# source_pcb.net
KiCad netlist of a schematic drawn in EasyEDA Pro
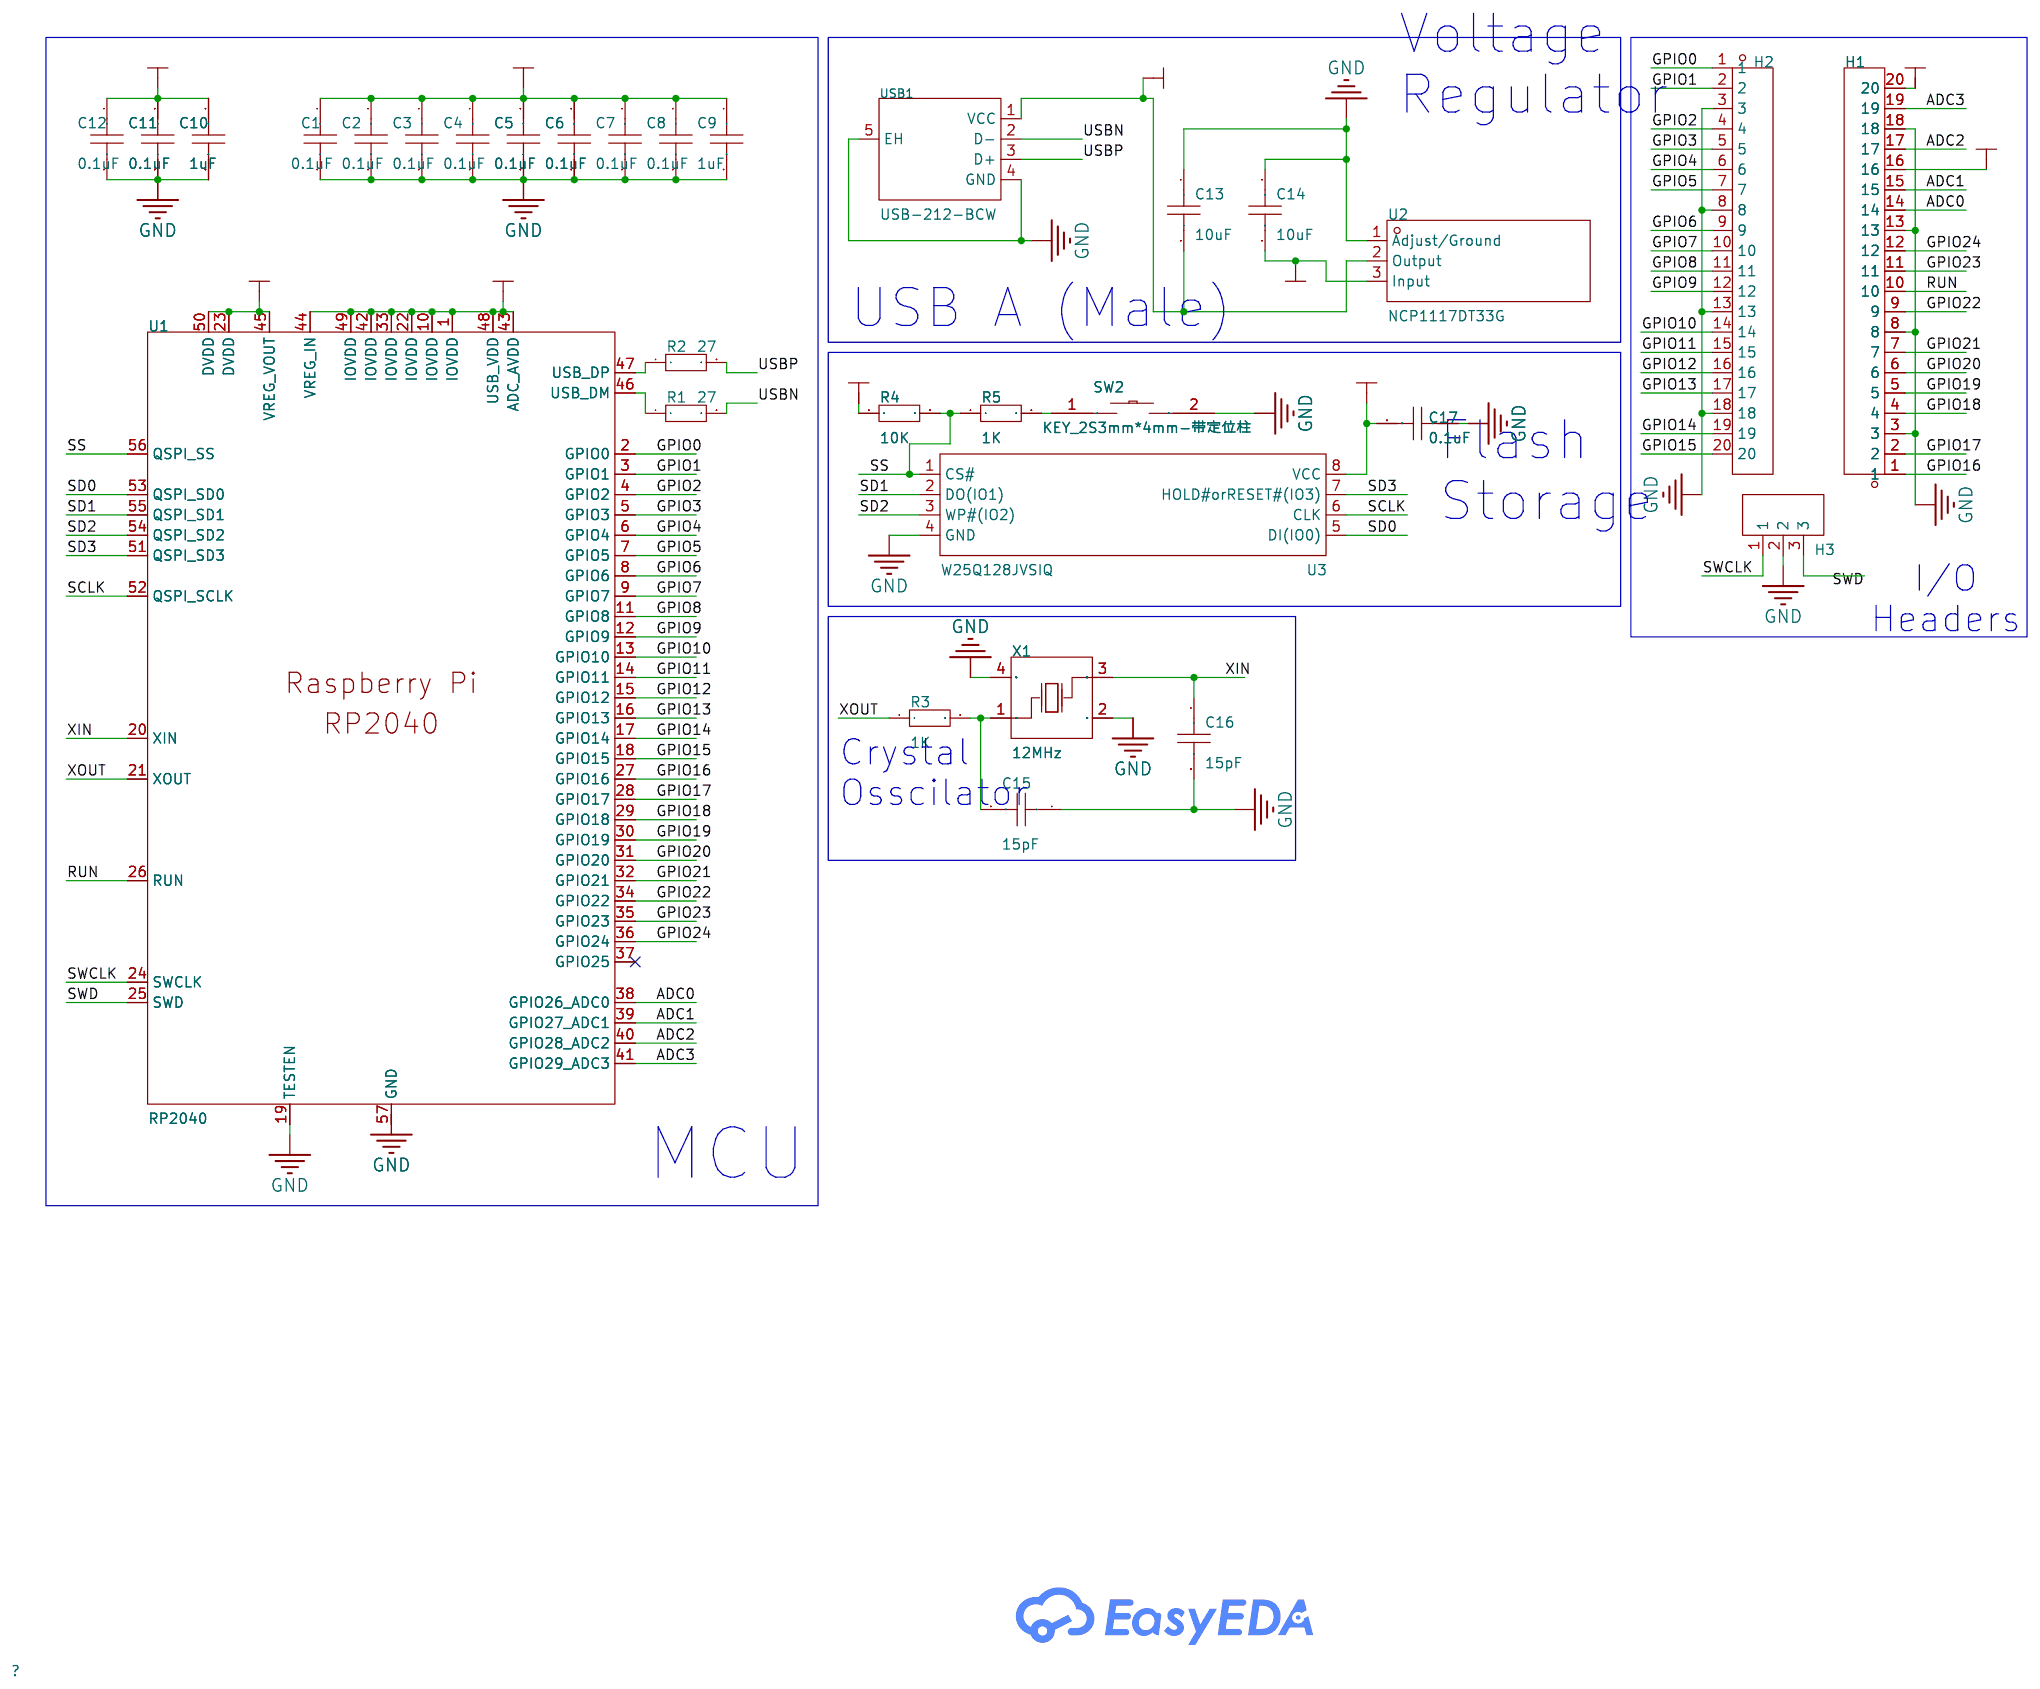
[diagram p0: schematic sheet]

(export (version "E")
  (design (tool "Eeschema 10.0.6"))
  (components
    (comp (ref "C1")
      (value "100nF")
      (footprint "easyedapro:C0603")
      (libsource (lib "easyedapro") (part "CAP"))
    )
    (comp (ref "C2")
      (value "100nF")
      (footprint "easyedapro:C0603")
      (libsource (lib "easyedapro") (part "CAP"))
    )
    (comp (ref "C3")
      (value "100nF")
      (footprint "easyedapro:C0603")
      (libsource (lib "easyedapro") (part "CAP"))
    )
    (comp (ref "C4")
      (value "100nF")
      (footprint "easyedapro:C0603")
      (libsource (lib "easyedapro") (part "CAP"))
    )
    (comp (ref "C5")
      (value "100nF")
      (footprint "easyedapro:C0603")
      (libsource (lib "easyedapro") (part "CAP"))
    )
    (comp (ref "C6")
      (value "100nF")
      (footprint "easyedapro:C0603")
      (libsource (lib "easyedapro") (part "CAP"))
    )
    (comp (ref "C7")
      (value "100nF")
      (footprint "easyedapro:C0603")
      (libsource (lib "easyedapro") (part "CAP"))
    )
    (comp (ref "C8")
      (value "100nF")
      (footprint "easyedapro:C0603")
      (libsource (lib "easyedapro") (part "CAP"))
    )
    (comp (ref "C9")
      (value "100nF")
      (footprint "easyedapro:C0603")
      (libsource (lib "easyedapro") (part "CAP"))
    )
    (comp (ref "C10")
      (value "100nF")
      (footprint "easyedapro:C0603")
      (libsource (lib "easyedapro") (part "CAP"))
    )
    (comp (ref "C11")
      (value "100nF")
      (footprint "easyedapro:C0603")
      (libsource (lib "easyedapro") (part "CAP"))
    )
    (comp (ref "C12")
      (value "100nF")
      (footprint "easyedapro:C0603")
      (libsource (lib "easyedapro") (part "CAP"))
    )
    (comp (ref "C13")
      (value "100nF")
      (footprint "easyedapro:C0603")
      (libsource (lib "easyedapro") (part "CAP"))
    )
    (comp (ref "C14")
      (value "100nF")
      (footprint "easyedapro:C0603")
      (libsource (lib "easyedapro") (part "CAP"))
    )
    (comp (ref "C15")
      (value "100nF")
      (footprint "easyedapro:C0603")
      (libsource (lib "easyedapro") (part "CAP"))
    )
    (comp (ref "C16")
      (value "100nF")
      (footprint "easyedapro:C0603")
      (libsource (lib "easyedapro") (part "CAP"))
    )
    (comp (ref "C17")
      (value "100nF")
      (footprint "easyedapro:C0603")
      (libsource (lib "easyedapro") (part "CAP"))
    )
    (comp (ref "H1")
      (value "~")
      (footprint "easyedapro:HDR-TH_20P-P2.54-V-M-1")
      (libsource (lib "easyedapro") (part "HDR_2.54-1x20P"))
    )
    (comp (ref "H2")
      (value "~")
      (footprint "easyedapro:HDR-TH_20P-P2.54-V-M-1")
      (libsource (lib "easyedapro") (part "HDR_2.54-1x20P"))
    )
    (comp (ref "H3")
      (value "~")
      (footprint "easyedapro:HDR-TH_3P-P2.54-V-M")
      (libsource (lib "easyedapro") (part "PZ254V-11-03P_C2937625"))
    )
    (comp (ref "R1") (value "10K") (footprint "easyedapro:R0603") (libsource (lib "easyedapro") (part "Res")))
    (comp (ref "R2") (value "10K") (footprint "easyedapro:R0603") (libsource (lib "easyedapro") (part "Res")))
    (comp (ref "R3") (value "10K") (footprint "easyedapro:R0603") (libsource (lib "easyedapro") (part "Res")))
    (comp (ref "R4") (value "10K") (footprint "easyedapro:R0603") (libsource (lib "easyedapro") (part "Res")))
    (comp (ref "R5") (value "10K") (footprint "easyedapro:R0603") (libsource (lib "easyedapro") (part "Res")))
    (comp (ref "SW2")
      (value "KEY_2S3mm*4mm-带定位柱")
      (footprint "easyedapro:KEY-SMD_L4.0-W3.7-LS4.8")
      (libsource (lib "easyedapro") (part "KEY_2S3MM*4MM-带定位柱"))
    )
    (comp (ref "U1")
      (value "RP2040")
      (footprint "easyedapro:QFN-56_L7.0-W7.0-P0.40-TL-EP4.0")
      (fields (field (name "Manufacturer") "Raspberry Pi(树莓派)"))
      (libsource (lib "easyedapro") (part "RP2040_C2961140"))
    )
    (comp (ref "U2")
      (value "NCP1117DT33G")
      (footprint "easyedapro:TO-252_L6.5-W6.1-P4.58-LS9.9-BR")
      (fields (field (name "Manufacturer") "onsemi(安森美)"))
      (libsource (lib "easyedapro") (part "NCP1117DT33G"))
    )
    (comp (ref "U3")
      (value "W25Q128JVSIQ")
      (footprint "easyedapro:SOIC-8_L5.3-W5.3-P1.27-LS8.0-BL")
      (fields (field (name "Manufacturer") "Winbond(华邦)"))
      (libsource (lib "easyedapro") (part "W25Q128JVSIQ"))
    )
    (comp (ref "USB1")
      (value "USB-212-BCW")
      (footprint "easyedapro:USB-A-SMD_USB-212-BCW")
      (fields (field (name "Manufacturer") "XUNPU(讯普)"))
      (libsource (lib "easyedapro") (part "USB-212-BCW"))
    )
    (comp (ref "X1")
      (value "12MHz")
      (footprint "easyedapro:CRYSTAL-SMD_4P-L3.2-W2.5-BL")
      (fields (field (name "Manufacturer Part") "X322512MSB4SI") (field (name "Manufacturer") "YXC(扬兴晶振)"))
      (libsource (lib "easyedapro") (part "X322512MSB4SI"))
    )
  )
  (nets
    (net (code "1") (name "+1.1V") (class "Default")
      (node (ref "C10") (pin "1") (pinfunction "1_1") (pintype "input"))
      (node (ref "C11") (pin "1") (pinfunction "1_1") (pintype "input"))
      (node (ref "C12") (pin "1") (pinfunction "1_1") (pintype "input"))
      (node (ref "U1") (pin "23") (pinfunction "DVDD_23") (pintype "bidirectional"))
      (node (ref "U1") (pin "45") (pinfunction "VREG_VOUT_45") (pintype "bidirectional"))
      (node (ref "U1") (pin "50") (pinfunction "DVDD_50") (pintype "bidirectional"))
    )
    (net (code "2") (name "+3.3V") (class "Default")
      (node (ref "C1") (pin "1") (pinfunction "1_1") (pintype "input"))
      (node (ref "C17") (pin "2") (pinfunction "2_2") (pintype "input"))
      (node (ref "C2") (pin "1") (pinfunction "1_1") (pintype "input"))
      (node (ref "C3") (pin "1") (pinfunction "1_1") (pintype "input"))
      (node (ref "C4") (pin "1") (pinfunction "1_1") (pintype "input"))
      (node (ref "C5") (pin "1") (pinfunction "1_1") (pintype "input"))
      (node (ref "C6") (pin "1") (pinfunction "1_1") (pintype "input"))
      (node (ref "C7") (pin "1") (pinfunction "1_1") (pintype "input"))
      (node (ref "C8") (pin "1") (pinfunction "1_1") (pintype "input"))
      (node (ref "C9") (pin "1") (pinfunction "1_1") (pintype "input"))
      (node (ref "R4") (pin "1") (pinfunction "1_1") (pintype "input"))
      (node (ref "U1") (pin "1") (pinfunction "IOVDD_1") (pintype "bidirectional"))
      (node (ref "U1") (pin "10") (pinfunction "IOVDD_10") (pintype "bidirectional"))
      (node (ref "U1") (pin "22") (pinfunction "IOVDD_22") (pintype "bidirectional"))
      (node (ref "U1") (pin "33") (pinfunction "IOVDD_33") (pintype "bidirectional"))
      (node (ref "U1") (pin "42") (pinfunction "IOVDD_42") (pintype "bidirectional"))
      (node (ref "U1") (pin "43") (pinfunction "ADC_AVDD_43") (pintype "bidirectional"))
      (node (ref "U1") (pin "44") (pinfunction "VREG_IN_44") (pintype "bidirectional"))
      (node (ref "U1") (pin "48") (pinfunction "USB_VDD_48") (pintype "bidirectional"))
      (node (ref "U1") (pin "49") (pinfunction "IOVDD_49") (pintype "bidirectional"))
      (node (ref "U3") (pin "8") (pinfunction "VCC_8") (pintype "unspecified"))
    )
    (net (code "3") (name "+3V3") (class "Default")
      (node (ref "C14") (pin "2") (pinfunction "2_2") (pintype "input"))
      (node (ref "H1") (pin "16") (pinfunction "16_16") (pintype "input"))
      (node (ref "U2") (pin "3") (pinfunction "Input_3") (pintype "unspecified"))
    )
    (net (code "4") (name "/ADC0") (class "Default")
      (node (ref "H1") (pin "14") (pinfunction "14_14") (pintype "input"))
      (node (ref "U1") (pin "38") (pinfunction "GPIO26_ADC0_38") (pintype "bidirectional"))
    )
    (net (code "5") (name "/ADC1") (class "Default")
      (node (ref "H1") (pin "15") (pinfunction "15_15") (pintype "input"))
      (node (ref "U1") (pin "39") (pinfunction "GPIO27_ADC1_39") (pintype "bidirectional"))
    )
    (net (code "6") (name "/ADC2") (class "Default")
      (node (ref "H1") (pin "17") (pinfunction "17_17") (pintype "input"))
      (node (ref "U1") (pin "40") (pinfunction "GPIO28_ADC2_40") (pintype "bidirectional"))
    )
    (net (code "7") (name "/ADC3") (class "Default")
      (node (ref "H1") (pin "19") (pinfunction "19_19") (pintype "input"))
      (node (ref "U1") (pin "41") (pinfunction "GPIO29_ADC3_41") (pintype "bidirectional"))
    )
    (net (code "8") (name "/GPIO0") (class "Default")
      (node (ref "H2") (pin "1") (pinfunction "1_1") (pintype "input"))
      (node (ref "U1") (pin "2") (pinfunction "GPIO0_2") (pintype "bidirectional"))
    )
    (net (code "9") (name "/GPIO1") (class "Default")
      (node (ref "H2") (pin "2") (pinfunction "2_2") (pintype "input"))
      (node (ref "U1") (pin "3") (pinfunction "GPIO1_3") (pintype "bidirectional"))
    )
    (net (code "10") (name "/GPIO2") (class "Default")
      (node (ref "H2") (pin "4") (pinfunction "4_4") (pintype "input"))
      (node (ref "U1") (pin "4") (pinfunction "GPIO2_4") (pintype "bidirectional"))
    )
    (net (code "11") (name "/GPIO3") (class "Default")
      (node (ref "H2") (pin "5") (pinfunction "5_5") (pintype "input"))
      (node (ref "U1") (pin "5") (pinfunction "GPIO3_5") (pintype "bidirectional"))
    )
    (net (code "12") (name "/GPIO4") (class "Default")
      (node (ref "H2") (pin "6") (pinfunction "6_6") (pintype "input"))
      (node (ref "U1") (pin "6") (pinfunction "GPIO4_6") (pintype "bidirectional"))
    )
    (net (code "13") (name "/GPIO5") (class "Default")
      (node (ref "H2") (pin "7") (pinfunction "7_7") (pintype "input"))
      (node (ref "U1") (pin "7") (pinfunction "GPIO5_7") (pintype "bidirectional"))
    )
    (net (code "14") (name "/GPIO6") (class "Default")
      (node (ref "H2") (pin "9") (pinfunction "9_9") (pintype "input"))
      (node (ref "U1") (pin "8") (pinfunction "GPIO6_8") (pintype "bidirectional"))
    )
    (net (code "15") (name "/GPIO7") (class "Default")
      (node (ref "H2") (pin "10") (pinfunction "10_10") (pintype "input"))
      (node (ref "U1") (pin "9") (pinfunction "GPIO7_9") (pintype "bidirectional"))
    )
    (net (code "16") (name "/GPIO8") (class "Default")
      (node (ref "H2") (pin "11") (pinfunction "11_11") (pintype "input"))
      (node (ref "U1") (pin "11") (pinfunction "GPIO8_11") (pintype "bidirectional"))
    )
    (net (code "17") (name "/GPIO9") (class "Default")
      (node (ref "H2") (pin "12") (pinfunction "12_12") (pintype "input"))
      (node (ref "U1") (pin "12") (pinfunction "GPIO9_12") (pintype "bidirectional"))
    )
    (net (code "18") (name "/GPIO10") (class "Default")
      (node (ref "H2") (pin "14") (pinfunction "14_14") (pintype "input"))
      (node (ref "U1") (pin "13") (pinfunction "GPIO10_13") (pintype "bidirectional"))
    )
    (net (code "19") (name "/GPIO11") (class "Default")
      (node (ref "H2") (pin "15") (pinfunction "15_15") (pintype "input"))
      (node (ref "U1") (pin "14") (pinfunction "GPIO11_14") (pintype "bidirectional"))
    )
    (net (code "20") (name "/GPIO12") (class "Default")
      (node (ref "H2") (pin "16") (pinfunction "16_16") (pintype "input"))
      (node (ref "U1") (pin "15") (pinfunction "GPIO12_15") (pintype "bidirectional"))
    )
    (net (code "21") (name "/GPIO13") (class "Default")
      (node (ref "H2") (pin "17") (pinfunction "17_17") (pintype "input"))
      (node (ref "U1") (pin "16") (pinfunction "GPIO13_16") (pintype "bidirectional"))
    )
    (net (code "22") (name "/GPIO14") (class "Default")
      (node (ref "H2") (pin "19") (pinfunction "19_19") (pintype "input"))
      (node (ref "U1") (pin "17") (pinfunction "GPIO14_17") (pintype "bidirectional"))
    )
    (net (code "23") (name "/GPIO15") (class "Default")
      (node (ref "H2") (pin "20") (pinfunction "20_20") (pintype "input"))
      (node (ref "U1") (pin "18") (pinfunction "GPIO15_18") (pintype "bidirectional"))
    )
    (net (code "24") (name "/GPIO16") (class "Default")
      (node (ref "H1") (pin "1") (pinfunction "1_1") (pintype "input"))
      (node (ref "U1") (pin "27") (pinfunction "GPIO16_27") (pintype "bidirectional"))
    )
    (net (code "25") (name "/GPIO17") (class "Default")
      (node (ref "H1") (pin "2") (pinfunction "2_2") (pintype "input"))
      (node (ref "U1") (pin "28") (pinfunction "GPIO17_28") (pintype "bidirectional"))
    )
    (net (code "26") (name "/GPIO18") (class "Default")
      (node (ref "H1") (pin "4") (pinfunction "4_4") (pintype "input"))
      (node (ref "U1") (pin "29") (pinfunction "GPIO18_29") (pintype "bidirectional"))
    )
    (net (code "27") (name "/GPIO19") (class "Default")
      (node (ref "H1") (pin "5") (pinfunction "5_5") (pintype "input"))
      (node (ref "U1") (pin "30") (pinfunction "GPIO19_30") (pintype "bidirectional"))
    )
    (net (code "28") (name "/GPIO20") (class "Default")
      (node (ref "H1") (pin "6") (pinfunction "6_6") (pintype "input"))
      (node (ref "U1") (pin "31") (pinfunction "GPIO20_31") (pintype "bidirectional"))
    )
    (net (code "29") (name "/GPIO21") (class "Default")
      (node (ref "H1") (pin "7") (pinfunction "7_7") (pintype "input"))
      (node (ref "U1") (pin "32") (pinfunction "GPIO21_32") (pintype "bidirectional"))
    )
    (net (code "30") (name "/GPIO22") (class "Default")
      (node (ref "H1") (pin "9") (pinfunction "9_9") (pintype "input"))
      (node (ref "U1") (pin "34") (pinfunction "GPIO22_34") (pintype "bidirectional"))
    )
    (net (code "31") (name "/GPIO23") (class "Default")
      (node (ref "H1") (pin "11") (pinfunction "11_11") (pintype "input"))
      (node (ref "U1") (pin "35") (pinfunction "GPIO23_35") (pintype "bidirectional"))
    )
    (net (code "32") (name "/GPIO24") (class "Default")
      (node (ref "H1") (pin "12") (pinfunction "12_12") (pintype "input"))
      (node (ref "U1") (pin "36") (pinfunction "GPIO24_36") (pintype "bidirectional"))
    )
    (net (code "33") (name "/RUN") (class "Default")
      (node (ref "H1") (pin "10") (pinfunction "10_10") (pintype "input"))
      (node (ref "U1") (pin "26") (pinfunction "RUN_26") (pintype "input"))
    )
    (net (code "34") (name "/SCLK") (class "Default")
      (node (ref "U1") (pin "52") (pinfunction "QSPI_SCLK_52") (pintype "output"))
      (node (ref "U3") (pin "6") (pinfunction "CLK_6") (pintype "unspecified"))
    )
    (net (code "35") (name "/SD0") (class "Default")
      (node (ref "U1") (pin "53") (pinfunction "QSPI_SD0_53") (pintype "bidirectional"))
      (node (ref "U3") (pin "5") (pinfunction "DI(IO0)_5") (pintype "unspecified"))
    )
    (net (code "36") (name "/SD1") (class "Default")
      (node (ref "U1") (pin "55") (pinfunction "QSPI_SD1_55") (pintype "bidirectional"))
      (node (ref "U3") (pin "2") (pinfunction "DO(IO1)_2") (pintype "unspecified"))
    )
    (net (code "37") (name "/SD2") (class "Default")
      (node (ref "U1") (pin "54") (pinfunction "QSPI_SD2_54") (pintype "bidirectional"))
      (node (ref "U3") (pin "3") (pinfunction "WP#(IO2)_3") (pintype "unspecified"))
    )
    (net (code "38") (name "/SD3") (class "Default")
      (node (ref "U1") (pin "51") (pinfunction "QSPI_SD3_51") (pintype "bidirectional"))
      (node (ref "U3") (pin "7") (pinfunction "HOLD#orRESET#(IO3)_7") (pintype "unspecified"))
    )
    (net (code "39") (name "/SS") (class "Default")
      (node (ref "R4") (pin "2") (pinfunction "2_2") (pintype "input"))
      (node (ref "R5") (pin "1") (pinfunction "1_1") (pintype "input"))
      (node (ref "U1") (pin "56") (pinfunction "QSPI_SS_56") (pintype "bidirectional"))
      (node (ref "U3") (pin "1") (pinfunction "CS#_1") (pintype "unspecified"))
    )
    (net (code "40") (name "/SWCLK") (class "Default")
      (node (ref "H3") (pin "1") (pinfunction "1_1") (pintype "unspecified"))
      (node (ref "U1") (pin "24") (pinfunction "SWCLK_24") (pintype "output"))
    )
    (net (code "41") (name "/SWD") (class "Default")
      (node (ref "H3") (pin "3") (pinfunction "3_3") (pintype "unspecified"))
      (node (ref "U1") (pin "25") (pinfunction "SWD_25") (pintype "bidirectional"))
    )
    (net (code "42") (name "/USBN") (class "Default")
      (node (ref "R1") (pin "2") (pinfunction "2_2") (pintype "input"))
      (node (ref "USB1") (pin "2") (pinfunction "D-_2") (pintype "input"))
    )
    (net (code "43") (name "/USBP") (class "Default")
      (node (ref "R2") (pin "2") (pinfunction "2_2") (pintype "input"))
      (node (ref "USB1") (pin "3") (pinfunction "D+_3") (pintype "input"))
    )
    (net (code "44") (name "/XIN") (class "Default")
      (node (ref "C16") (pin "1") (pinfunction "1_1") (pintype "input"))
      (node (ref "U1") (pin "20") (pinfunction "XIN_20") (pintype "input"))
      (node (ref "X1") (pin "3") (pinfunction "OSC2_3") (pintype "unspecified"))
    )
    (net (code "45") (name "/XOUT") (class "Default")
      (node (ref "R3") (pin "1") (pinfunction "1_1") (pintype "input"))
      (node (ref "U1") (pin "21") (pinfunction "XOUT_21") (pintype "unspecified"))
    )
    (net (code "46") (name "GND") (class "Default")
      (node (ref "C1") (pin "2") (pinfunction "2_2") (pintype "input"))
      (node (ref "C10") (pin "2") (pinfunction "2_2") (pintype "input"))
      (node (ref "C11") (pin "2") (pinfunction "2_2") (pintype "input"))
      (node (ref "C12") (pin "2") (pinfunction "2_2") (pintype "input"))
      (node (ref "C13") (pin "1") (pinfunction "1_1") (pintype "input"))
      (node (ref "C14") (pin "1") (pinfunction "1_1") (pintype "input"))
      (node (ref "C15") (pin "1") (pinfunction "1_1") (pintype "input"))
      (node (ref "C16") (pin "2") (pinfunction "2_2") (pintype "input"))
      (node (ref "C17") (pin "1") (pinfunction "1_1") (pintype "input"))
      (node (ref "C2") (pin "2") (pinfunction "2_2") (pintype "input"))
      (node (ref "C3") (pin "2") (pinfunction "2_2") (pintype "input"))
      (node (ref "C4") (pin "2") (pinfunction "2_2") (pintype "input"))
      (node (ref "C5") (pin "2") (pinfunction "2_2") (pintype "input"))
      (node (ref "C6") (pin "2") (pinfunction "2_2") (pintype "input"))
      (node (ref "C7") (pin "2") (pinfunction "2_2") (pintype "input"))
      (node (ref "C8") (pin "2") (pinfunction "2_2") (pintype "input"))
      (node (ref "C9") (pin "2") (pinfunction "2_2") (pintype "input"))
      (node (ref "H1") (pin "13") (pinfunction "13_13") (pintype "input"))
      (node (ref "H1") (pin "18") (pinfunction "18_18") (pintype "input"))
      (node (ref "H1") (pin "3") (pinfunction "3_3") (pintype "input"))
      (node (ref "H1") (pin "8") (pinfunction "8_8") (pintype "input"))
      (node (ref "H2") (pin "13") (pinfunction "13_13") (pintype "input"))
      (node (ref "H2") (pin "18") (pinfunction "18_18") (pintype "input"))
      (node (ref "H2") (pin "3") (pinfunction "3_3") (pintype "input"))
      (node (ref "H2") (pin "8") (pinfunction "8_8") (pintype "input"))
      (node (ref "H3") (pin "2") (pinfunction "2_2") (pintype "unspecified"))
      (node (ref "SW2") (pin "2") (pinfunction "2_2") (pintype "unspecified"))
      (node (ref "U1") (pin "19") (pinfunction "TESTEN_19") (pintype "unspecified"))
      (node (ref "U1") (pin "57") (pinfunction "GND_57") (pintype "bidirectional"))
      (node (ref "U2") (pin "1") (pinfunction "Adjust/Ground_1") (pintype "unspecified"))
      (node (ref "U3") (pin "4") (pinfunction "GND_4") (pintype "unspecified"))
      (node (ref "USB1") (pin "4") (pinfunction "GND_4") (pintype "input"))
      (node (ref "USB1") (pin "5") (pinfunction "EH_5") (pintype "input"))
      (node (ref "X1") (pin "2") (pinfunction "GND_2") (pintype "unspecified"))
      (node (ref "X1") (pin "4") (pinfunction "GND_4") (pintype "unspecified"))
    )
    (net (code "47") (name "Net-(R5-Pad2)") (class "Default")
      (node (ref "R5") (pin "2") (pinfunction "2_2") (pintype "input"))
      (node (ref "SW2") (pin "1") (pinfunction "1_1") (pintype "unspecified"))
    )
    (net (code "48") (name "Net-(U1-USB_DM)") (class "Default")
      (node (ref "R1") (pin "1") (pinfunction "1_1") (pintype "input"))
      (node (ref "U1") (pin "46") (pinfunction "USB_DM_46") (pintype "bidirectional"))
    )
    (net (code "49") (name "Net-(U1-USB_DP)") (class "Default")
      (node (ref "R2") (pin "1") (pinfunction "1_1") (pintype "input"))
      (node (ref "U1") (pin "47") (pinfunction "USB_DP_47") (pintype "bidirectional"))
    )
    (net (code "50") (name "Net-(X1-OSC1)") (class "Default")
      (node (ref "C15") (pin "2") (pinfunction "2_2") (pintype "input"))
      (node (ref "R3") (pin "2") (pinfunction "2_2") (pintype "input"))
      (node (ref "X1") (pin "1") (pinfunction "OSC1_1") (pintype "unspecified"))
    )
    (net (code "51") (name "VBUS") (class "Default")
      (node (ref "C13") (pin "2") (pinfunction "2_2") (pintype "input"))
      (node (ref "H1") (pin "20") (pinfunction "20_20") (pintype "input"))
      (node (ref "U2") (pin "2") (pinfunction "Output_2") (pintype "unspecified"))
      (node (ref "USB1") (pin "1") (pinfunction "VCC_1") (pintype "input"))
    )
    (net (code "52") (name "unconnected-(U1-GPIO25-Pad37)") (class "Default")
      (node (ref "U1") (pin "37") (pinfunction "GPIO25_37") (pintype "bidirectional+no_connect"))
    )
  )
)
